# SOC_mcu.net
KiCad netlist of a schematic drawn in EAGLE
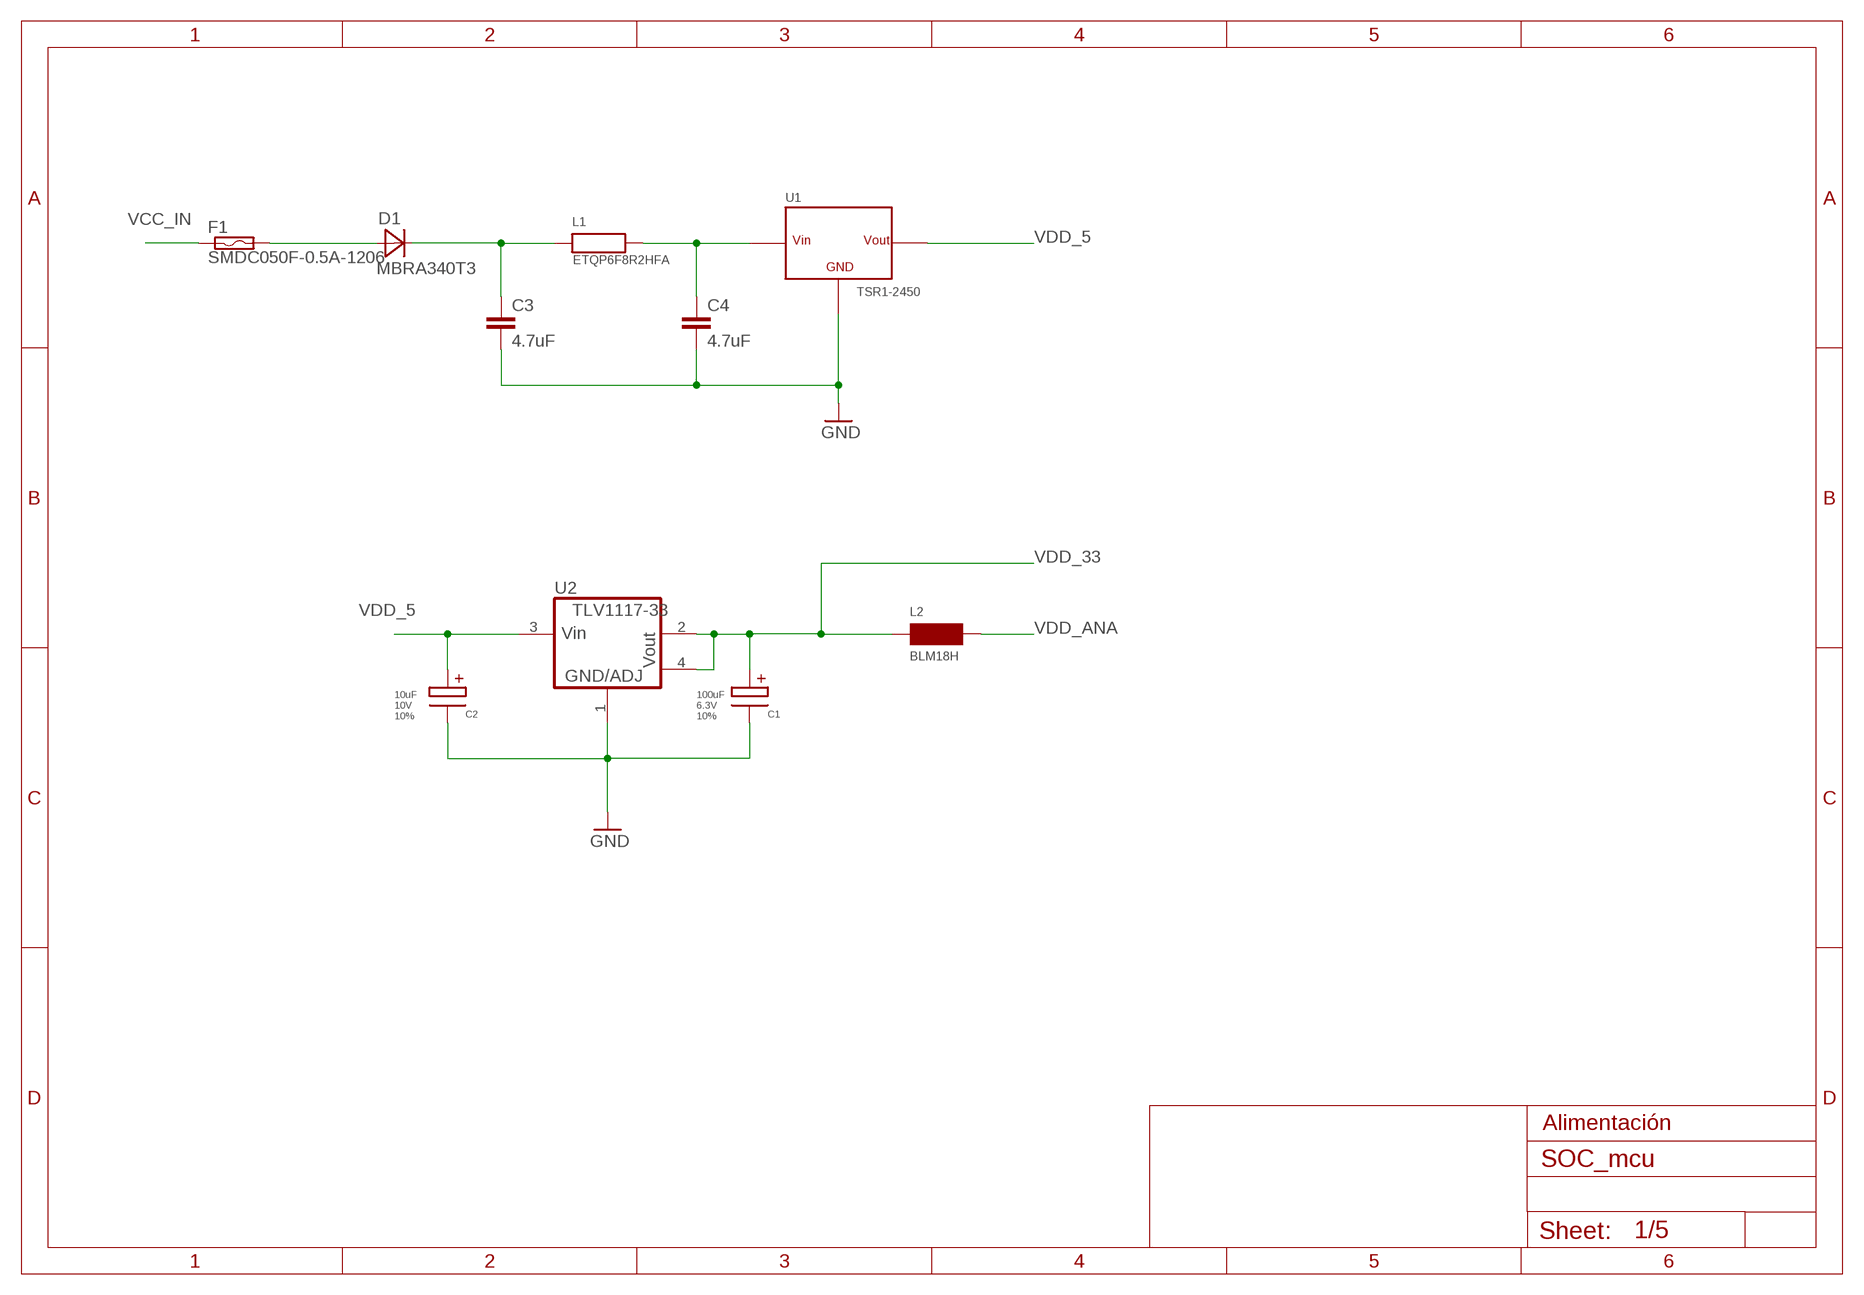
[diagram p0: schematic, sheet 1]
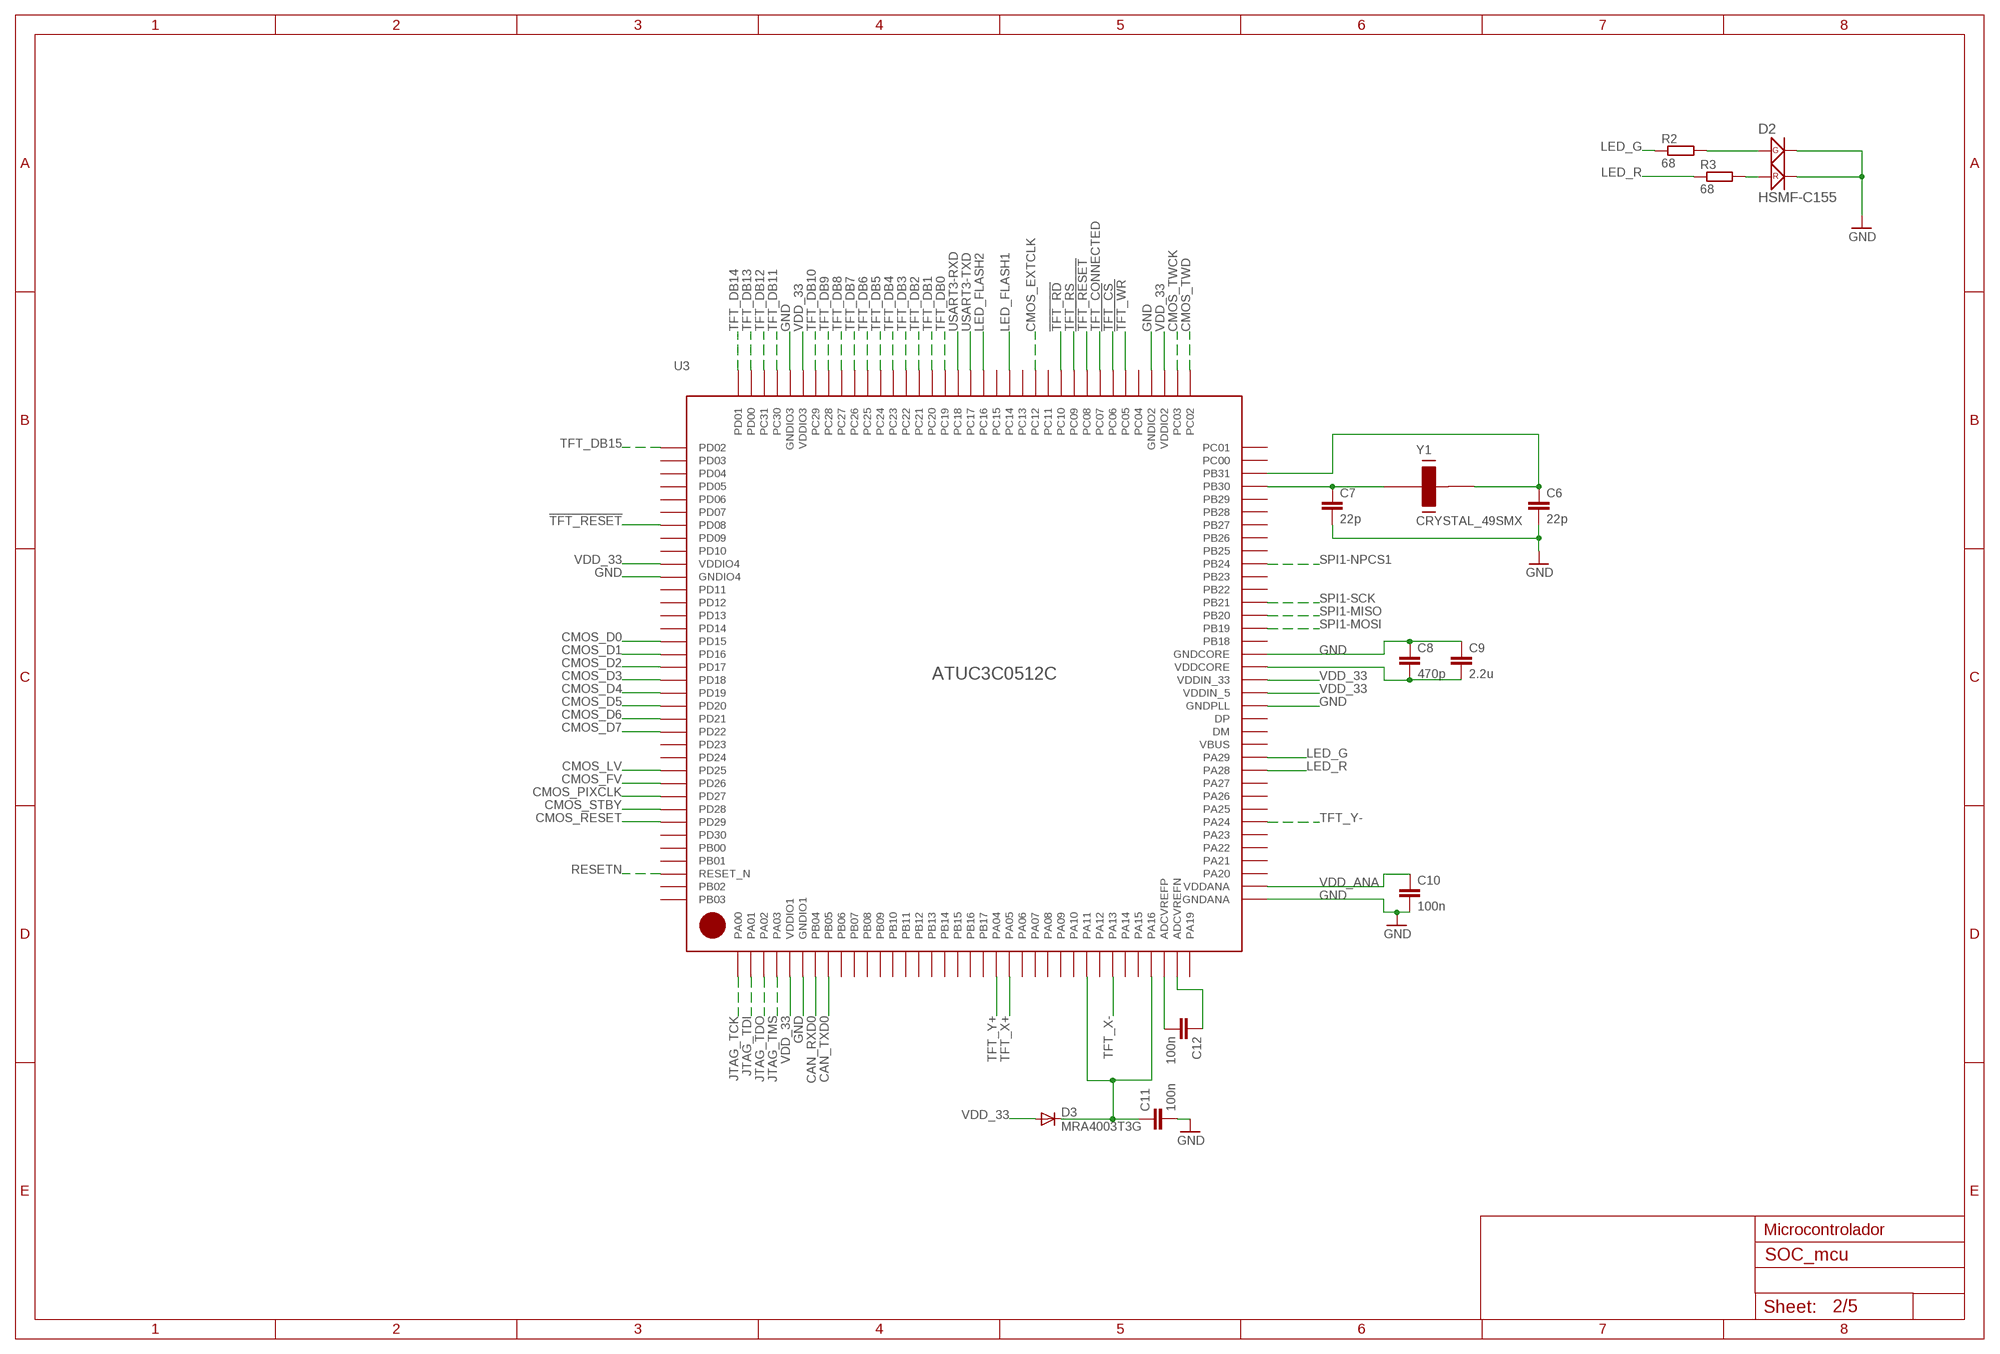
[diagram p1: schematic, sheet 2]
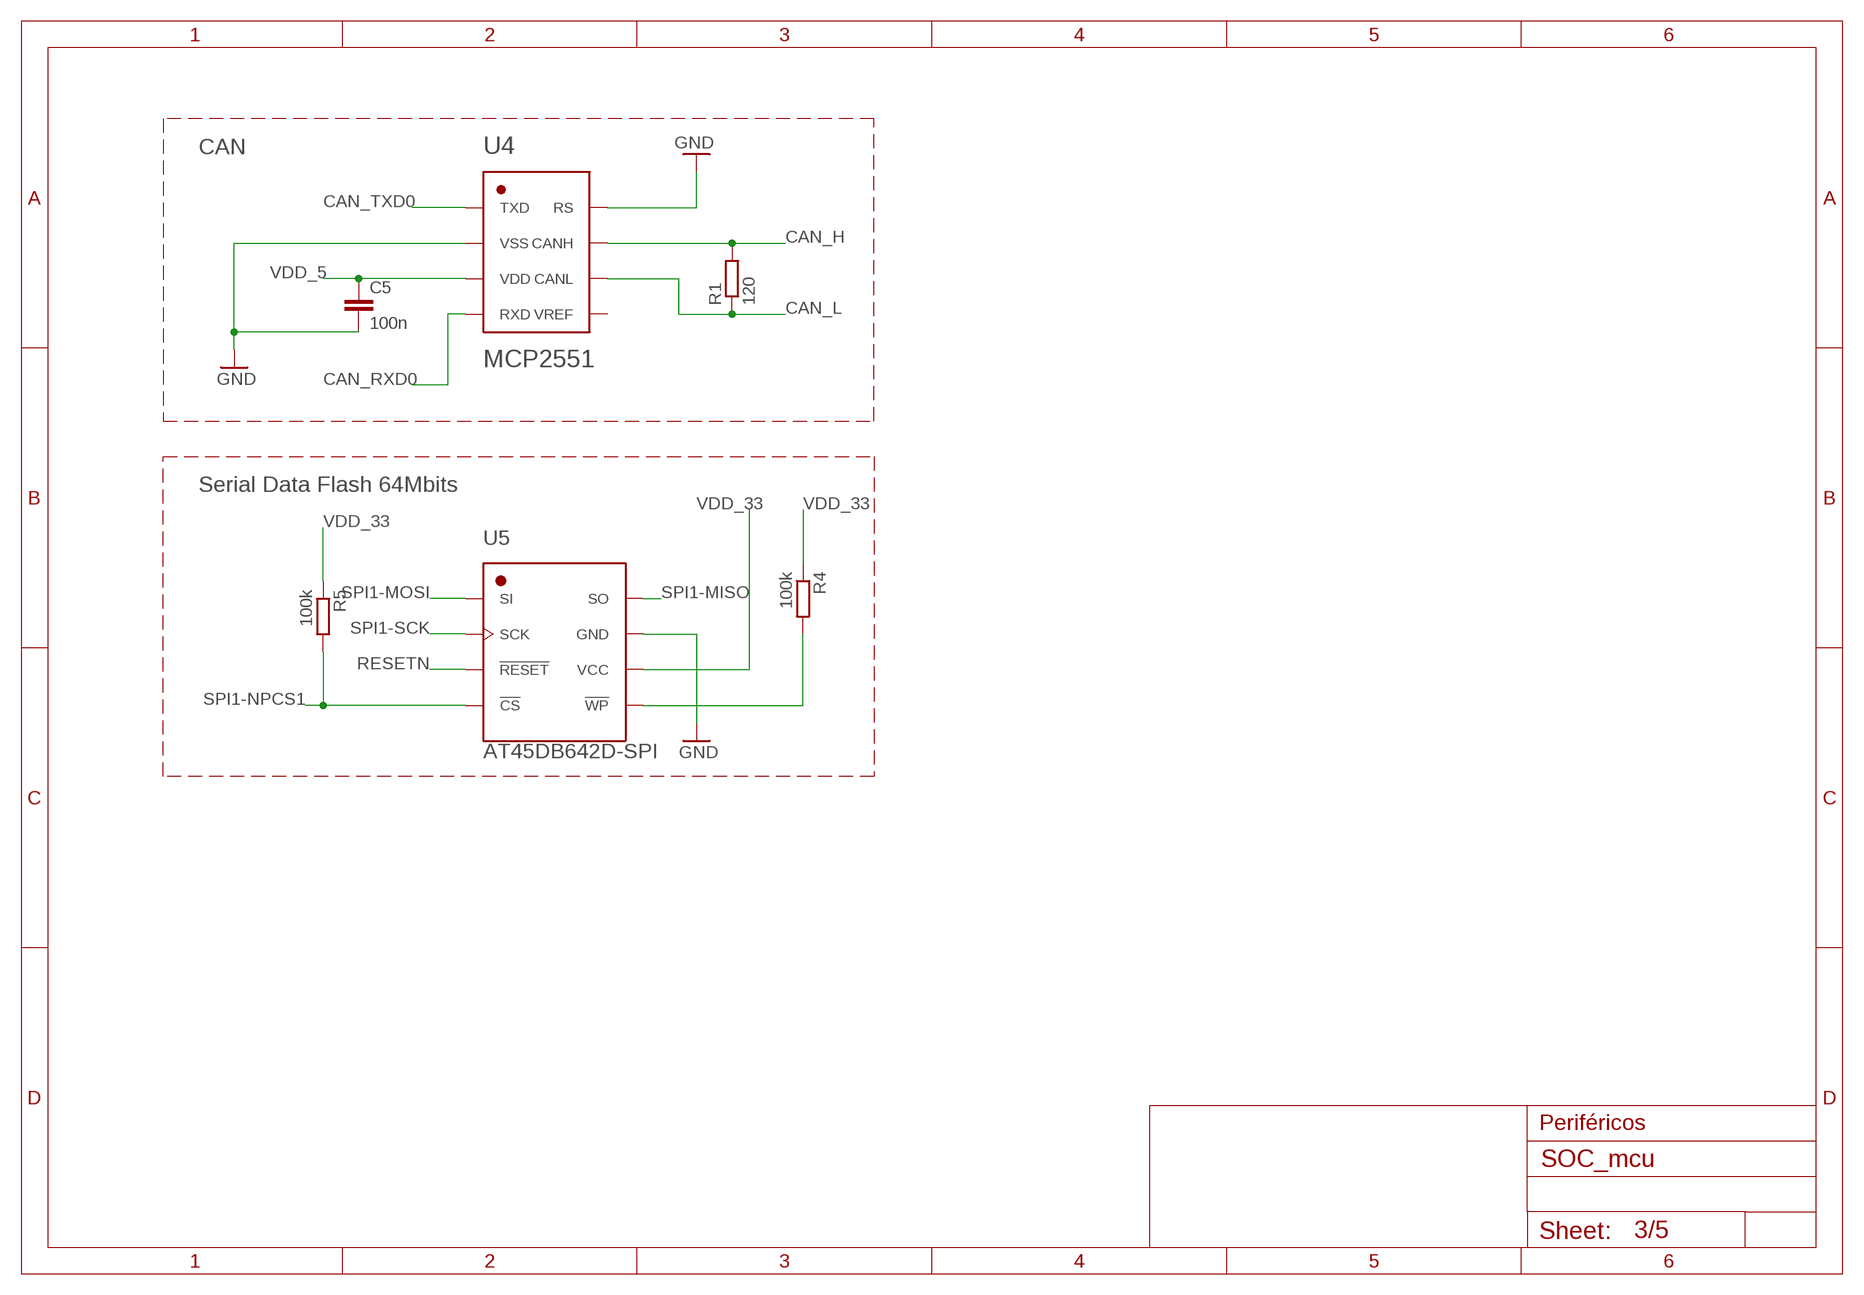
[diagram p2: schematic, sheet 3]
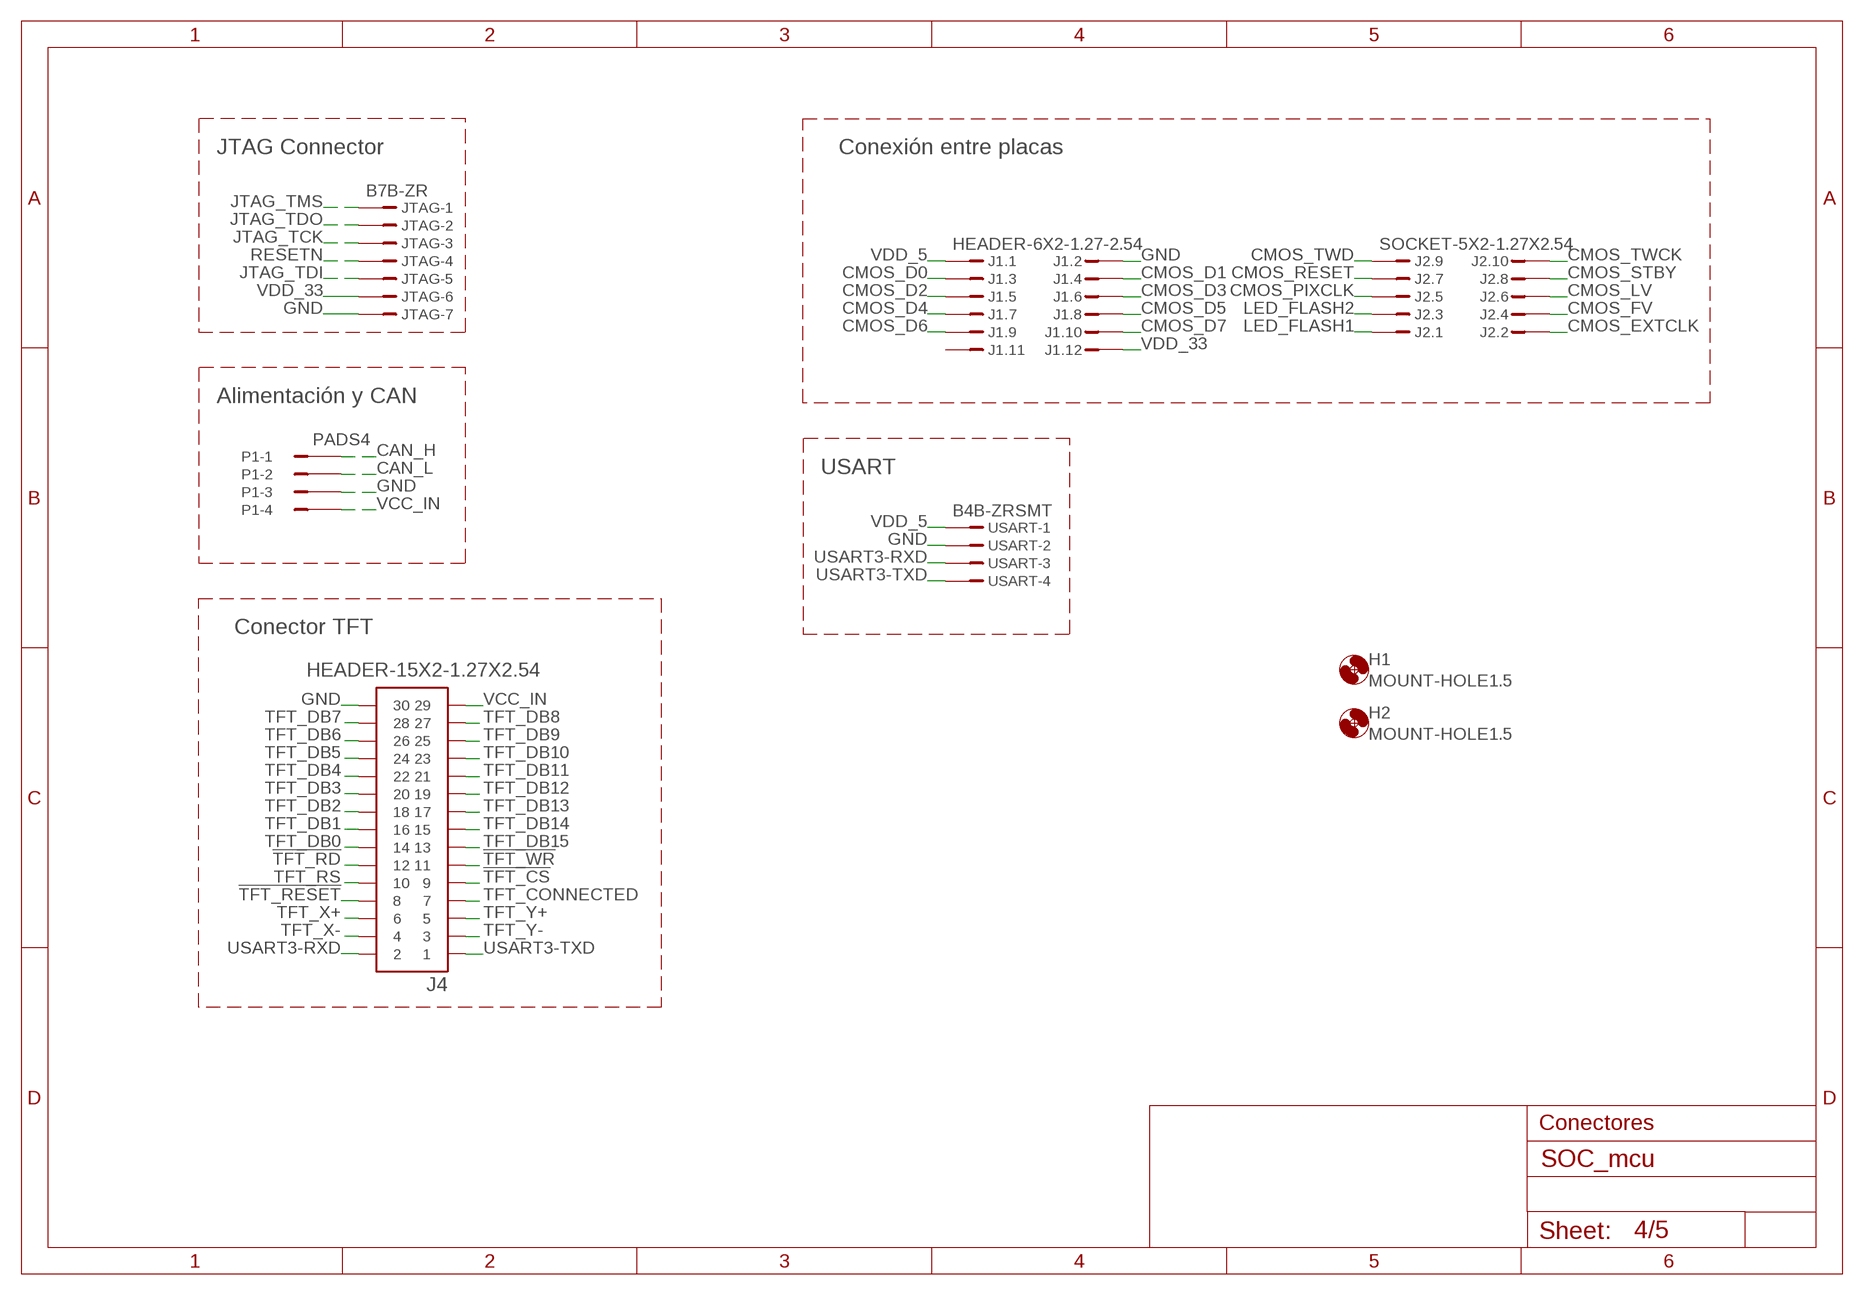
[diagram p3: schematic, sheet 4]
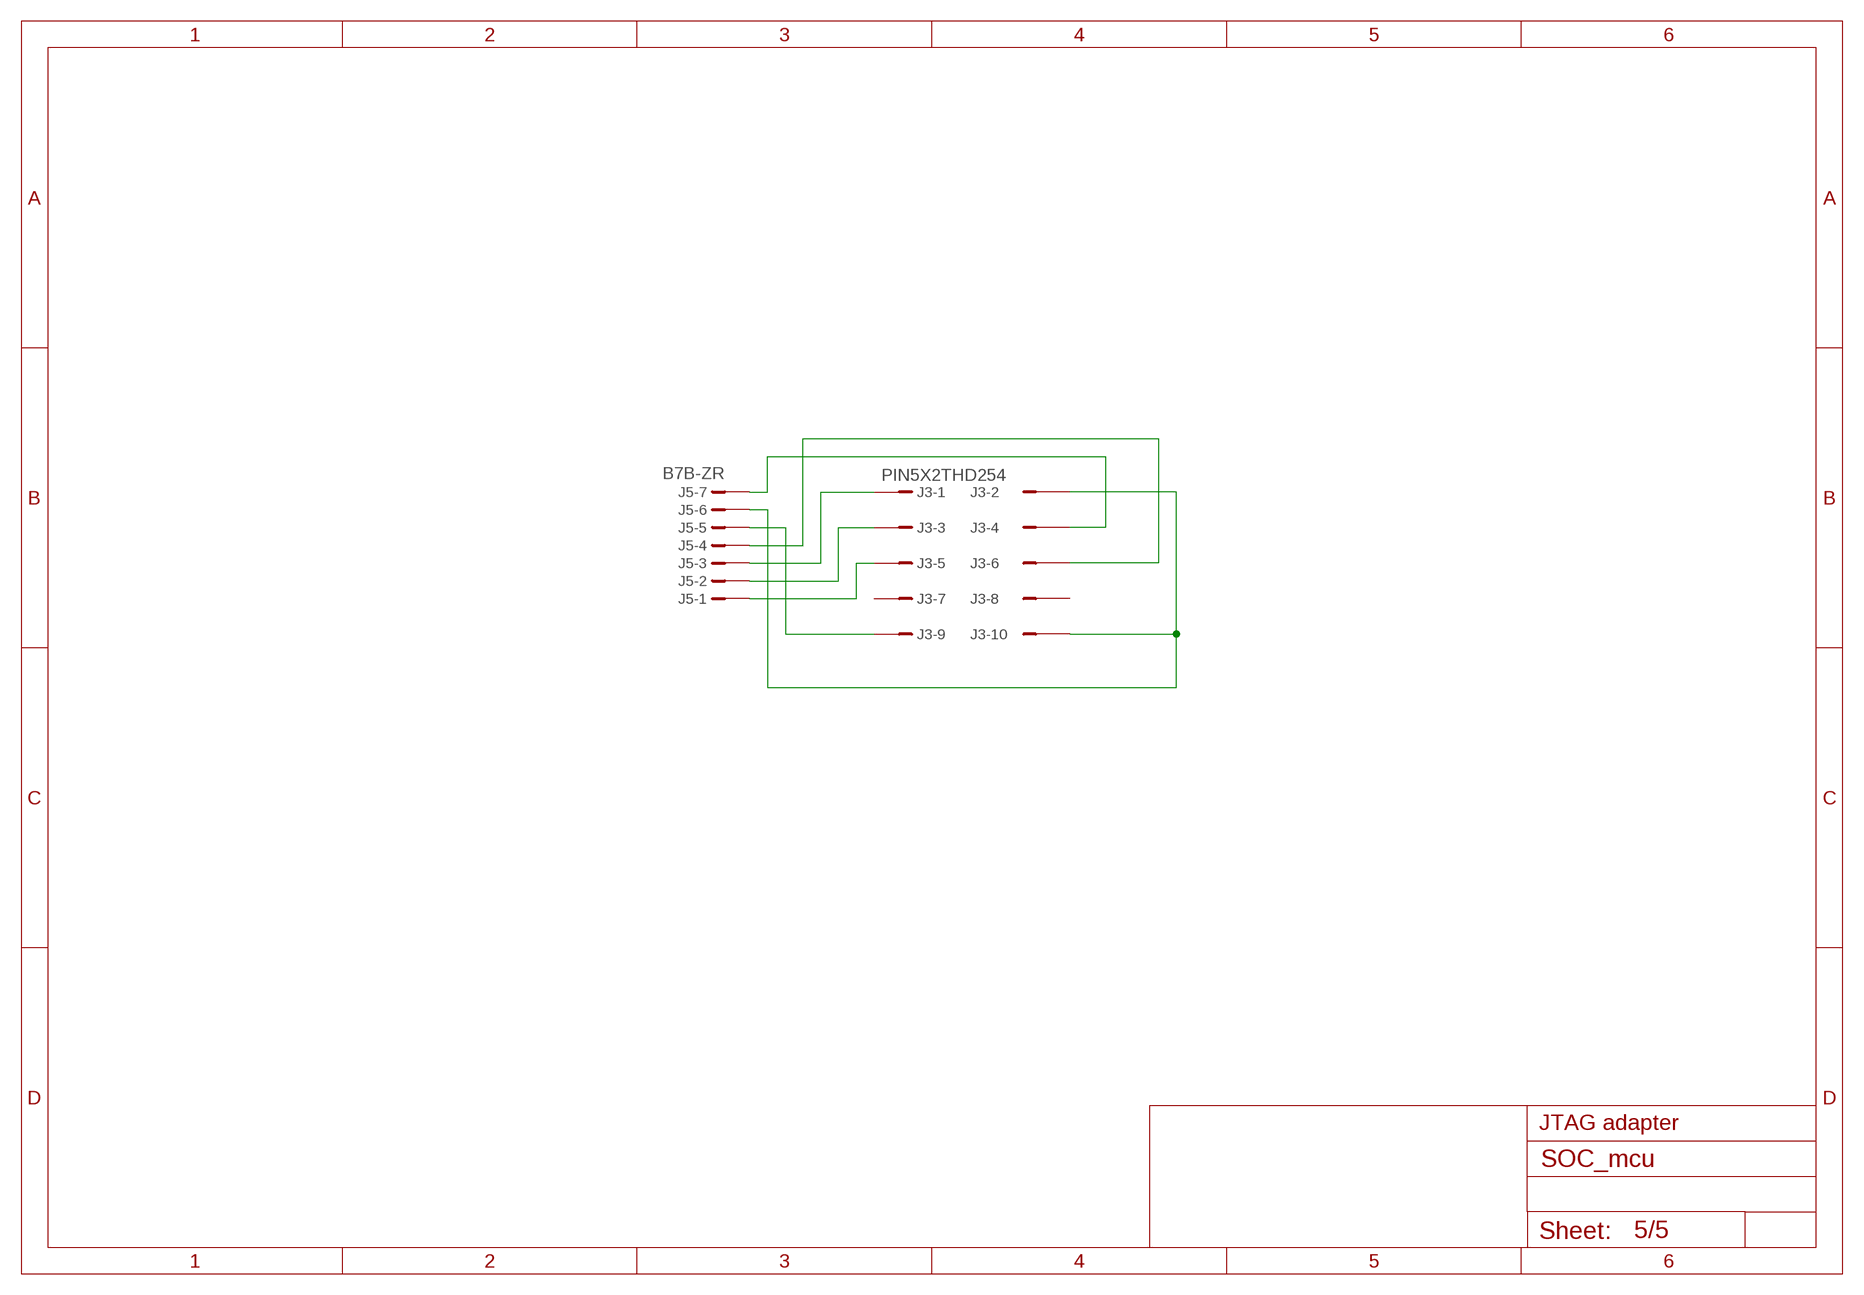
[diagram p4: schematic, sheet 5]

(export (version "E")
  (design (tool "Eeschema 10.0.6"))
  (components
    (comp (ref "C5")
      (value "100n")
      (footprint "eagle-import:C0603")
      (libsource (lib "eagle-import") (part "C-EUC0603"))
    )
    (comp (ref "R1")
      (value "120")
      (footprint "eagle-import:R0805")
      (libsource (lib "eagle-import") (part "R-EU_R0805"))
    )
    (comp (ref "R4")
      (value "100k")
      (footprint "eagle-import:R0603")
      (libsource (lib "eagle-import") (part "R-EU_R0603"))
    )
    (comp (ref "R5")
      (value "100k")
      (footprint "eagle-import:R0603")
      (libsource (lib "eagle-import") (part "R-EU_R0603"))
    )
    (comp (ref "U4")
      (value "MCP2551")
      (footprint "eagle-import:SO08")
      (libsource (lib "eagle-import") (part "MCP2551"))
    )
    (comp (ref "U5")
      (value "AT45DB642D-SPI")
      (footprint "eagle-import:8CN3")
      (libsource (lib "eagle-import") (part "AT45DB642D-SPI"))
    )
    (comp (ref "C1")
      (value "100uF")
      (footprint "eagle-import:3528-21")
      (fields
        (field (name "MPN") "293D107X96R3B2TE3")
        (field (name "TOLERANCE") "10%")
        (field (name "VOLTAGE") "6.3V")
      )
      (libsource (lib "eagle-import") (part "C293DB100U-6V3-10%-"))
    )
    (comp (ref "C2")
      (value "10uF")
      (footprint "eagle-import:3528-21")
      (fields
        (field (name "MPN") "293D106X9010B2TE3")
        (field (name "TOLERANCE") "10%")
        (field (name "VOLTAGE") "10V")
      )
      (libsource (lib "eagle-import") (part "C293DB10U-10V-10%-"))
    )
    (comp (ref "C3")
      (value "4.7uF")
      (footprint "eagle-import:C0805")
      (libsource (lib "eagle-import") (part "C-EUC0805"))
    )
    (comp (ref "C4")
      (value "4.7uF")
      (footprint "eagle-import:C0805")
      (libsource (lib "eagle-import") (part "C-EUC0805"))
    )
    (comp (ref "D1")
      (value "MBRA340T3")
      (footprint "eagle-import:SMA")
      (libsource (lib "eagle-import") (part "MBRA340T3"))
    )
    (comp (ref "F1")
      (value "SMDC050F-0.5A-1206")
      (footprint "eagle-import:1206")
      (fields (field (name "MPN") "NANOSMDC050F/13.2"))
      (libsource (lib "eagle-import") (part "SMDC050F-12060.5A-"))
    )
    (comp (ref "L1")
      (value "ETQP6F8R2HFA")
      (footprint "eagle-import:PAN_COIL_CHOKE")
      (libsource (lib "eagle-import") (part "ETQP6F8R2HFA"))
    )
    (comp (ref "L2")
      (value "BLM18H")
      (footprint "eagle-import:0603")
      (libsource (lib "eagle-import") (part "BLM18H"))
    )
    (comp (ref "U1")
      (value "TSR1-2450")
      (footprint "eagle-import:TO220V")
      (libsource (lib "eagle-import") (part "TSR1-2450"))
    )
    (comp (ref "U2")
      (value "TLV1117-33")
      (footprint "eagle-import:SOT223")
      (fields
        (field (name "MPN") "TLV1117-CDCY")
        (field (name "MPN_1") "TLV1117-CDCY")
        (field (name "OC_FARNELL") "1494942")
        (field (name "OC_RS") "660-7975 ")
      )
      (libsource (lib "eagle-import") (part "REG111733"))
    )
    (comp (ref "C6")
      (value "22p")
      (footprint "eagle-import:C0603")
      (libsource (lib "eagle-import") (part "C-EUC0603"))
    )
    (comp (ref "C7")
      (value "22p")
      (footprint "eagle-import:C0603")
      (libsource (lib "eagle-import") (part "C-EUC0603"))
    )
    (comp (ref "C8")
      (value "470p")
      (footprint "eagle-import:C0603")
      (libsource (lib "eagle-import") (part "C-EUC0603"))
    )
    (comp (ref "C9")
      (value "2.2u")
      (footprint "eagle-import:C0603")
      (libsource (lib "eagle-import") (part "C-EUC0603"))
    )
    (comp (ref "C10")
      (value "100n")
      (footprint "eagle-import:C0603")
      (libsource (lib "eagle-import") (part "C-EUC0603"))
    )
    (comp (ref "C11")
      (value "100n")
      (footprint "eagle-import:C0603")
      (libsource (lib "eagle-import") (part "C-EUC0603"))
    )
    (comp (ref "C12")
      (value "100n")
      (footprint "eagle-import:C0603")
      (libsource (lib "eagle-import") (part "C-EUC0603"))
    )
    (comp (ref "D2")
      (value "HSMF-C155")
      (footprint "eagle-import:HSMF-C")
      (libsource (lib "eagle-import") (part "HSMF-C155"))
    )
    (comp (ref "D3")
      (value "MRA4003T3G")
      (footprint "eagle-import:DO214AC")
      (libsource (lib "eagle-import") (part "DIODE-DO214AC"))
    )
    (comp (ref "R2")
      (value "68")
      (footprint "eagle-import:R0603")
      (libsource (lib "eagle-import") (part "R-EU_R0603"))
    )
    (comp (ref "R3")
      (value "68")
      (footprint "eagle-import:R0603")
      (libsource (lib "eagle-import") (part "R-EU_R0603"))
    )
    (comp (ref "U3")
      (value "ATUC3C0512C")
      (footprint "eagle-import:TQFP144")
      (libsource (lib "eagle-import") (part "ATUC3C0512C"))
    )
    (comp (ref "Y1")
      (value "CRYSTAL_49SMX")
      (footprint "eagle-import:HC49UP")
      (libsource (lib "eagle-import") (part "CRYSTAL_49SMX"))
    )
    (comp (ref "J3")
      (value "PIN5X2THD254")
      (footprint "eagle-import:5X2THD254")
      (libsource (lib "eagle-import") (part "PIN5X2THD254"))
    )
    (comp (ref "J5")
      (value "B7B-ZR")
      (footprint "eagle-import:B7B-ZR")
      (libsource (lib "eagle-import") (part "B7B-ZR"))
    )
    (comp (ref "H1")
      (value "MOUNT-HOLE1.5")
      (footprint "eagle-import:1,5")
      (libsource (lib "eagle-import") (part "MOUNT-HOLE1.5"))
    )
    (comp (ref "H2")
      (value "MOUNT-HOLE1.5")
      (footprint "eagle-import:1,5")
      (libsource (lib "eagle-import") (part "MOUNT-HOLE1.5"))
    )
    (comp (ref "J1")
      (value "HEADER-6X2-1.27-2.54")
      (footprint "eagle-import:HEADER-THD-6X2(1.27X2.54)")
      (libsource (lib "eagle-import") (part "HEADER-6X2-1.27-2.54"))
    )
    (comp (ref "J2")
      (value "SOCKET-5X2-1.27X2.54")
      (footprint "eagle-import:SOCKET-THD-5X2(1.27X2.54)")
      (libsource (lib "eagle-import") (part "SOCKET-5X2-1.27X2.54"))
    )
    (comp (ref "J4")
      (value "HEADER-15X2-1.27X2.54")
      (footprint "eagle-import:HEADER-THD-15X2(1.27X2.54)")
      (libsource (lib "eagle-import") (part "HEADER-15X2-1.27X2.54"))
    )
    (comp (ref "JTAG")
      (value "B7B-ZR")
      (footprint "eagle-import:B7B-ZR")
      (libsource (lib "eagle-import") (part "B7B-ZR"))
    )
    (comp (ref "P1")
      (value "PADS4")
      (footprint "eagle-import:CAN+POWER")
      (libsource (lib "eagle-import") (part "PAD-4"))
    )
    (comp (ref "USART")
      (value "B4B-ZRSMT")
      (footprint "eagle-import:SM4-TF")
      (libsource (lib "eagle-import") (part "B4B-ZRSMT"))
    )
  )
  (nets
    (net (code "1") (name "CAN_H") (class "Default")
      (node (ref "P1") (pin "1") (pinfunction "1_1") (pintype "passive"))
      (node (ref "R1") (pin "2") (pinfunction "2_2") (pintype "passive"))
      (node (ref "U4") (pin "7") (pinfunction "CANH_7") (pintype "bidirectional"))
    )
    (net (code "2") (name "CAN_L") (class "Default")
      (node (ref "P1") (pin "2") (pinfunction "1_2") (pintype "passive"))
      (node (ref "R1") (pin "1") (pinfunction "1_1") (pintype "passive"))
      (node (ref "U4") (pin "6") (pinfunction "CANL_6") (pintype "bidirectional"))
    )
    (net (code "3") (name "CAN_RXD0") (class "Default")
      (node (ref "U3") (pin "7") (pinfunction "PB04_7") (pintype "bidirectional"))
      (node (ref "U4") (pin "4") (pinfunction "RXD_4") (pintype "bidirectional"))
    )
    (net (code "4") (name "CAN_TXD0") (class "Default")
      (node (ref "U3") (pin "8") (pinfunction "PB05_8") (pintype "bidirectional"))
      (node (ref "U4") (pin "1") (pinfunction "TXD_1") (pintype "bidirectional"))
    )
    (net (code "5") (name "CMOS_D0") (class "Default")
      (node (ref "J1") (pin "3") (pinfunction "1_3") (pintype "passive"))
      (node (ref "U3") (pin "124") (pinfunction "PD15_124") (pintype "bidirectional"))
    )
    (net (code "6") (name "CMOS_D1") (class "Default")
      (node (ref "J1") (pin "4") (pinfunction "1_4") (pintype "passive"))
      (node (ref "U3") (pin "125") (pinfunction "PD16_125") (pintype "bidirectional"))
    )
    (net (code "7") (name "CMOS_D2") (class "Default")
      (node (ref "J1") (pin "5") (pinfunction "1_5") (pintype "passive"))
      (node (ref "U3") (pin "126") (pinfunction "PD17_126") (pintype "bidirectional"))
    )
    (net (code "8") (name "CMOS_D3") (class "Default")
      (node (ref "J1") (pin "6") (pinfunction "1_6") (pintype "passive"))
      (node (ref "U3") (pin "127") (pinfunction "PD18_127") (pintype "bidirectional"))
    )
    (net (code "9") (name "CMOS_D4") (class "Default")
      (node (ref "J1") (pin "7") (pinfunction "1_7") (pintype "passive"))
      (node (ref "U3") (pin "128") (pinfunction "PD19_128") (pintype "bidirectional"))
    )
    (net (code "10") (name "CMOS_D5") (class "Default")
      (node (ref "J1") (pin "8") (pinfunction "1_8") (pintype "passive"))
      (node (ref "U3") (pin "129") (pinfunction "PD20_129") (pintype "bidirectional"))
    )
    (net (code "11") (name "CMOS_D6") (class "Default")
      (node (ref "J1") (pin "9") (pinfunction "1_9") (pintype "passive"))
      (node (ref "U3") (pin "130") (pinfunction "PD21_130") (pintype "bidirectional"))
    )
    (net (code "12") (name "CMOS_D7") (class "Default")
      (node (ref "J1") (pin "10") (pinfunction "1_10") (pintype "passive"))
      (node (ref "U3") (pin "131") (pinfunction "PD22_131") (pintype "bidirectional"))
    )
    (net (code "13") (name "CMOS_EXTCLK") (class "Default")
      (node (ref "J2") (pin "P2") (pinfunction "1_P2") (pintype "passive"))
      (node (ref "U3") (pin "85") (pinfunction "PC12_85") (pintype "bidirectional"))
    )
    (net (code "14") (name "CMOS_FV") (class "Default")
      (node (ref "J2") (pin "P4") (pinfunction "1_P4") (pintype "passive"))
      (node (ref "U3") (pin "135") (pinfunction "PD26_135") (pintype "bidirectional"))
    )
    (net (code "15") (name "CMOS_LV") (class "Default")
      (node (ref "J2") (pin "P6") (pinfunction "1_P6") (pintype "passive"))
      (node (ref "U3") (pin "134") (pinfunction "PD25_134") (pintype "bidirectional"))
    )
    (net (code "16") (name "CMOS_PIXCLK") (class "Default")
      (node (ref "J2") (pin "P5") (pinfunction "1_P5") (pintype "passive"))
      (node (ref "U3") (pin "136") (pinfunction "PD27_136") (pintype "bidirectional"))
    )
    (net (code "17") (name "CMOS_RESET") (class "Default")
      (node (ref "J2") (pin "P7") (pinfunction "1_P7") (pintype "passive"))
      (node (ref "U3") (pin "138") (pinfunction "PD29_138") (pintype "bidirectional"))
    )
    (net (code "18") (name "CMOS_STBY") (class "Default")
      (node (ref "J2") (pin "P8") (pinfunction "1_P8") (pintype "passive"))
      (node (ref "U3") (pin "137") (pinfunction "PD28_137") (pintype "bidirectional"))
    )
    (net (code "19") (name "CMOS_TWCK") (class "Default")
      (node (ref "J2") (pin "P10") (pinfunction "1_P10") (pintype "passive"))
      (node (ref "U3") (pin "74") (pinfunction "PC03_74") (pintype "bidirectional"))
    )
    (net (code "20") (name "CMOS_TWD") (class "Default")
      (node (ref "J2") (pin "P9") (pinfunction "1_P9") (pintype "passive"))
      (node (ref "U3") (pin "73") (pinfunction "PC02_73") (pintype "bidirectional"))
    )
    (net (code "21") (name "GND") (class "Default")
      (node (ref "C1") (pin "NEG") (pinfunction "NEG_NEG") (pintype "bidirectional"))
      (node (ref "C10") (pin "2") (pinfunction "2_2") (pintype "passive"))
      (node (ref "C11") (pin "2") (pinfunction "2_2") (pintype "passive"))
      (node (ref "C2") (pin "NEG") (pinfunction "NEG_NEG") (pintype "bidirectional"))
      (node (ref "C3") (pin "2") (pinfunction "2_2") (pintype "passive"))
      (node (ref "C4") (pin "2") (pinfunction "2_2") (pintype "passive"))
      (node (ref "C5") (pin "2") (pinfunction "2_2") (pintype "passive"))
      (node (ref "C6") (pin "2") (pinfunction "2_2") (pintype "passive"))
      (node (ref "C7") (pin "2") (pinfunction "2_2") (pintype "passive"))
      (node (ref "C8") (pin "1") (pinfunction "1_1") (pintype "passive"))
      (node (ref "C9") (pin "1") (pinfunction "1_1") (pintype "passive"))
      (node (ref "D2") (pin "2") (pinfunction "2_2") (pintype "bidirectional"))
      (node (ref "D2") (pin "4") (pinfunction "4_4") (pintype "bidirectional"))
      (node (ref "J1") (pin "2") (pinfunction "1_2") (pintype "passive"))
      (node (ref "J4") (pin "30") (pinfunction "30_30") (pintype "bidirectional"))
      (node (ref "JTAG") (pin "7") (pinfunction "1_7") (pintype "passive"))
      (node (ref "P1") (pin "3") (pinfunction "1_3") (pintype "passive"))
      (node (ref "U1") (pin "2") (pinfunction "GND_2") (pintype "bidirectional"))
      (node (ref "U2") (pin "1") (pinfunction "GND_1") (pintype "bidirectional"))
      (node (ref "U3") (pin "104") (pinfunction "GNDIO3_104") (pintype "bidirectional"))
      (node (ref "U3") (pin "119") (pinfunction "GNDIO4_119") (pintype "bidirectional"))
      (node (ref "U3") (pin "37") (pinfunction "GNDANA_37") (pintype "bidirectional"))
      (node (ref "U3") (pin "52") (pinfunction "GNDPLL_52") (pintype "bidirectional"))
      (node (ref "U3") (pin "56") (pinfunction "GNDCORE_56") (pintype "bidirectional"))
      (node (ref "U3") (pin "6") (pinfunction "GNDIO1_6") (pintype "bidirectional"))
      (node (ref "U3") (pin "76") (pinfunction "GNDIO2_76") (pintype "bidirectional"))
      (node (ref "U4") (pin "2") (pinfunction "VSS_2") (pintype "bidirectional"))
      (node (ref "U4") (pin "8") (pinfunction "RS_8") (pintype "bidirectional"))
      (node (ref "U5") (pin "7") (pinfunction "GND_7") (pintype "bidirectional"))
      (node (ref "USART") (pin "2") (pinfunction "1_2") (pintype "passive"))
    )
    (net (code "22") (name "JTAG_TCK") (class "Default")
      (node (ref "JTAG") (pin "3") (pinfunction "1_3") (pintype "passive"))
      (node (ref "U3") (pin "1") (pinfunction "PA00_1") (pintype "bidirectional"))
    )
    (net (code "23") (name "JTAG_TDI") (class "Default")
      (node (ref "JTAG") (pin "5") (pinfunction "1_5") (pintype "passive"))
      (node (ref "U3") (pin "2") (pinfunction "PA01_2") (pintype "bidirectional"))
    )
    (net (code "24") (name "JTAG_TDO") (class "Default")
      (node (ref "JTAG") (pin "2") (pinfunction "1_2") (pintype "passive"))
      (node (ref "U3") (pin "3") (pinfunction "PA02_3") (pintype "bidirectional"))
    )
    (net (code "25") (name "JTAG_TMS") (class "Default")
      (node (ref "JTAG") (pin "1") (pinfunction "1_1") (pintype "passive"))
      (node (ref "U3") (pin "4") (pinfunction "PA03_4") (pintype "bidirectional"))
    )
    (net (code "26") (name "LED_FLASH1") (class "Default")
      (node (ref "J2") (pin "P1") (pinfunction "1_P1") (pintype "passive"))
      (node (ref "U3") (pin "87") (pinfunction "PC14_87") (pintype "bidirectional"))
    )
    (net (code "27") (name "LED_FLASH2") (class "Default")
      (node (ref "J2") (pin "P3") (pinfunction "1_P3") (pintype "passive"))
      (node (ref "U3") (pin "89") (pinfunction "PC16_89") (pintype "bidirectional"))
    )
    (net (code "28") (name "LED_G") (class "Default")
      (node (ref "R2") (pin "1") (pinfunction "1_1") (pintype "passive"))
      (node (ref "U3") (pin "48") (pinfunction "PA29_48") (pintype "bidirectional"))
    )
    (net (code "29") (name "LED_R") (class "Default")
      (node (ref "R3") (pin "1") (pinfunction "1_1") (pintype "passive"))
      (node (ref "U3") (pin "47") (pinfunction "PA28_47") (pintype "bidirectional"))
    )
    (net (code "30") (name "Net-(D1-PadA)") (class "Default")
      (node (ref "D1") (pin "A") (pinfunction "A_A") (pintype "passive"))
      (node (ref "F1") (pin "2") (pinfunction "2_2") (pintype "passive"))
    )
    (net (code "31") (name "Net-(D2-Pad1)") (class "Default")
      (node (ref "D2") (pin "1") (pinfunction "1_1") (pintype "bidirectional"))
      (node (ref "R2") (pin "2") (pinfunction "2_2") (pintype "passive"))
    )
    (net (code "32") (name "Net-(D2-Pad3)") (class "Default")
      (node (ref "D2") (pin "3") (pinfunction "3_3") (pintype "bidirectional"))
      (node (ref "R3") (pin "2") (pinfunction "2_2") (pintype "passive"))
    )
    (net (code "33") (name "Net-(J3B-1)") (class "Default")
      (node (ref "J3") (pin "10") (pinfunction "1_10") (pintype "passive"))
      (node (ref "J3") (pin "2") (pinfunction "1_2") (pintype "passive"))
      (node (ref "J5") (pin "6") (pinfunction "1_6") (pintype "passive"))
    )
    (net (code "34") (name "Net-(J3D-1)") (class "Default")
      (node (ref "J3") (pin "3") (pinfunction "1_3") (pintype "passive"))
      (node (ref "J5") (pin "2") (pinfunction "1_2") (pintype "passive"))
    )
    (net (code "35") (name "Net-(J3E-1)") (class "Default")
      (node (ref "J3") (pin "4") (pinfunction "1_4") (pintype "passive"))
      (node (ref "J5") (pin "7") (pinfunction "1_7") (pintype "passive"))
    )
    (net (code "36") (name "Net-(J3F-1)") (class "Default")
      (node (ref "J3") (pin "5") (pinfunction "1_5") (pintype "passive"))
      (node (ref "J5") (pin "1") (pinfunction "1_1") (pintype "passive"))
    )
    (net (code "37") (name "Net-(J3G-1)") (class "Default")
      (node (ref "J3") (pin "6") (pinfunction "1_6") (pintype "passive"))
      (node (ref "J5") (pin "4") (pinfunction "1_4") (pintype "passive"))
    )
    (net (code "38") (name "Net-(J3J-1)") (class "Default")
      (node (ref "J3") (pin "9") (pinfunction "1_9") (pintype "passive"))
      (node (ref "J5") (pin "5") (pinfunction "1_5") (pintype "passive"))
    )
    (net (code "39") (name "Net-(J5C-1)") (class "Default")
      (node (ref "J3") (pin "1") (pinfunction "1_1") (pintype "passive"))
      (node (ref "J5") (pin "3") (pinfunction "1_3") (pintype "passive"))
    )
    (net (code "40") (name "Net-(L1-P$1)") (class "Default")
      (node (ref "C3") (pin "1") (pinfunction "1_1") (pintype "passive"))
      (node (ref "D1") (pin "C") (pinfunction "C_C") (pintype "passive"))
      (node (ref "L1") (pin "1") (pinfunction "P$1_1") (pintype "bidirectional"))
    )
    (net (code "41") (name "Net-(L1-P$2)") (class "Default")
      (node (ref "C4") (pin "1") (pinfunction "1_1") (pintype "passive"))
      (node (ref "L1") (pin "2") (pinfunction "P$2_2") (pintype "bidirectional"))
      (node (ref "U1") (pin "1") (pinfunction "+VIN_1") (pintype "bidirectional"))
    )
    (net (code "42") (name "Net-(U3-ADCVREFN)") (class "Default")
      (node (ref "C12") (pin "1") (pinfunction "1_1") (pintype "passive"))
      (node (ref "U3") (pin "35") (pinfunction "ADCVREFN_35") (pintype "bidirectional"))
    )
    (net (code "43") (name "Net-(U3-ADCVREFP)") (class "Default")
      (node (ref "C12") (pin "2") (pinfunction "2_2") (pintype "passive"))
      (node (ref "U3") (pin "34") (pinfunction "ADCVREFP_34") (pintype "bidirectional"))
    )
    (net (code "44") (name "Net-(U3-PA11)") (class "Default")
      (node (ref "C11") (pin "1") (pinfunction "1_1") (pintype "passive"))
      (node (ref "D3") (pin "C") (pinfunction "C_C") (pintype "passive"))
      (node (ref "U3") (pin "28") (pinfunction "PA11_28") (pintype "bidirectional"))
      (node (ref "U3") (pin "33") (pinfunction "PA16_33") (pintype "bidirectional"))
    )
    (net (code "45") (name "Net-(U3-PB30)") (class "Default")
      (node (ref "C7") (pin "1") (pinfunction "1_1") (pintype "passive"))
      (node (ref "U3") (pin "69") (pinfunction "PB30_69") (pintype "bidirectional"))
      (node (ref "Y1") (pin "1") (pinfunction "1_1") (pintype "bidirectional"))
    )
    (net (code "46") (name "Net-(U3-PB31)") (class "Default")
      (node (ref "C6") (pin "1") (pinfunction "1_1") (pintype "passive"))
      (node (ref "U3") (pin "70") (pinfunction "PB31_70") (pintype "bidirectional"))
      (node (ref "Y1") (pin "2") (pinfunction "2_2") (pintype "bidirectional"))
    )
    (net (code "47") (name "Net-(U3-VDDCORE)") (class "Default")
      (node (ref "C8") (pin "2") (pinfunction "2_2") (pintype "passive"))
      (node (ref "C9") (pin "2") (pinfunction "2_2") (pintype "passive"))
      (node (ref "U3") (pin "55") (pinfunction "VDDCORE_55") (pintype "bidirectional"))
    )
    (net (code "48") (name "Net-(U5-~{WP})") (class "Default")
      (node (ref "R4") (pin "2") (pinfunction "2_2") (pintype "passive"))
      (node (ref "U5") (pin "5") (pinfunction "~{WP}_5") (pintype "bidirectional"))
    )
    (net (code "49") (name "RESETN") (class "Default")
      (node (ref "JTAG") (pin "4") (pinfunction "1_4") (pintype "passive"))
      (node (ref "U3") (pin "142") (pinfunction "RESET_N_142") (pintype "bidirectional"))
      (node (ref "U5") (pin "3") (pinfunction "~{RESET}_3") (pintype "bidirectional"))
    )
    (net (code "50") (name "SPI1-MISO") (class "Default")
      (node (ref "U3") (pin "59") (pinfunction "PB20_59") (pintype "bidirectional"))
      (node (ref "U5") (pin "8") (pinfunction "SO_8") (pintype "bidirectional"))
    )
    (net (code "51") (name "SPI1-MOSI") (class "Default")
      (node (ref "U3") (pin "58") (pinfunction "PB19_58") (pintype "bidirectional"))
      (node (ref "U5") (pin "1") (pinfunction "SI_1") (pintype "bidirectional"))
    )
    (net (code "52") (name "SPI1-NPCS1") (class "Default")
      (node (ref "R5") (pin "2") (pinfunction "2_2") (pintype "passive"))
      (node (ref "U3") (pin "63") (pinfunction "PB24_63") (pintype "bidirectional"))
      (node (ref "U5") (pin "4") (pinfunction "~{CS}_4") (pintype "bidirectional"))
    )
    (net (code "53") (name "SPI1-SCK") (class "Default")
      (node (ref "U3") (pin "60") (pinfunction "PB21_60") (pintype "bidirectional"))
      (node (ref "U5") (pin "2") (pinfunction "SCK_2") (pintype "bidirectional"))
    )
    (net (code "54") (name "TFT_CONNECTED") (class "Default")
      (node (ref "J4") (pin "7") (pinfunction "7_7") (pintype "bidirectional"))
      (node (ref "U3") (pin "80") (pinfunction "PC07_80") (pintype "bidirectional"))
    )
    (net (code "55") (name "TFT_DB0") (class "Default")
      (node (ref "J4") (pin "14") (pinfunction "14_14") (pintype "bidirectional"))
      (node (ref "U3") (pin "92") (pinfunction "PC19_92") (pintype "bidirectional"))
    )
    (net (code "56") (name "TFT_DB1") (class "Default")
      (node (ref "J4") (pin "16") (pinfunction "16_16") (pintype "bidirectional"))
      (node (ref "U3") (pin "93") (pinfunction "PC20_93") (pintype "bidirectional"))
    )
    (net (code "57") (name "TFT_DB2") (class "Default")
      (node (ref "J4") (pin "18") (pinfunction "18_18") (pintype "bidirectional"))
      (node (ref "U3") (pin "94") (pinfunction "PC21_94") (pintype "bidirectional"))
    )
    (net (code "58") (name "TFT_DB3") (class "Default")
      (node (ref "J4") (pin "20") (pinfunction "20_20") (pintype "bidirectional"))
      (node (ref "U3") (pin "95") (pinfunction "PC22_95") (pintype "bidirectional"))
    )
    (net (code "59") (name "TFT_DB4") (class "Default")
      (node (ref "J4") (pin "22") (pinfunction "22_22") (pintype "bidirectional"))
      (node (ref "U3") (pin "96") (pinfunction "PC23_96") (pintype "bidirectional"))
    )
    (net (code "60") (name "TFT_DB5") (class "Default")
      (node (ref "J4") (pin "24") (pinfunction "24_24") (pintype "bidirectional"))
      (node (ref "U3") (pin "97") (pinfunction "PC24_97") (pintype "bidirectional"))
    )
    (net (code "61") (name "TFT_DB6") (class "Default")
      (node (ref "J4") (pin "26") (pinfunction "26_26") (pintype "bidirectional"))
      (node (ref "U3") (pin "98") (pinfunction "PC25_98") (pintype "bidirectional"))
    )
    (net (code "62") (name "TFT_DB7") (class "Default")
      (node (ref "J4") (pin "28") (pinfunction "28_28") (pintype "bidirectional"))
      (node (ref "U3") (pin "99") (pinfunction "PC26_99") (pintype "bidirectional"))
    )
    (net (code "63") (name "TFT_DB8") (class "Default")
      (node (ref "J4") (pin "27") (pinfunction "27_27") (pintype "bidirectional"))
      (node (ref "U3") (pin "100") (pinfunction "PC27_100") (pintype "bidirectional"))
    )
    (net (code "64") (name "TFT_DB9") (class "Default")
      (node (ref "J4") (pin "25") (pinfunction "25_25") (pintype "bidirectional"))
      (node (ref "U3") (pin "101") (pinfunction "PC28_101") (pintype "bidirectional"))
    )
    (net (code "65") (name "TFT_DB10") (class "Default")
      (node (ref "J4") (pin "23") (pinfunction "23_23") (pintype "bidirectional"))
      (node (ref "U3") (pin "102") (pinfunction "PC29_102") (pintype "bidirectional"))
    )
    (net (code "66") (name "TFT_DB11") (class "Default")
      (node (ref "J4") (pin "21") (pinfunction "21_21") (pintype "bidirectional"))
      (node (ref "U3") (pin "105") (pinfunction "PC30_105") (pintype "bidirectional"))
    )
    (net (code "67") (name "TFT_DB12") (class "Default")
      (node (ref "J4") (pin "19") (pinfunction "19_19") (pintype "bidirectional"))
      (node (ref "U3") (pin "106") (pinfunction "PC31_106") (pintype "bidirectional"))
    )
    (net (code "68") (name "TFT_DB13") (class "Default")
      (node (ref "J4") (pin "17") (pinfunction "17_17") (pintype "bidirectional"))
      (node (ref "U3") (pin "107") (pinfunction "PD00_107") (pintype "bidirectional"))
    )
    (net (code "69") (name "TFT_DB14") (class "Default")
      (node (ref "J4") (pin "15") (pinfunction "15_15") (pintype "bidirectional"))
      (node (ref "U3") (pin "108") (pinfunction "PD01_108") (pintype "bidirectional"))
    )
    (net (code "70") (name "TFT_DB15") (class "Default")
      (node (ref "J4") (pin "13") (pinfunction "13_13") (pintype "bidirectional"))
      (node (ref "U3") (pin "109") (pinfunction "PD02_109") (pintype "bidirectional"))
    )
    (net (code "71") (name "TFT_RS") (class "Default")
      (node (ref "J4") (pin "10") (pinfunction "10_10") (pintype "bidirectional"))
      (node (ref "U3") (pin "82") (pinfunction "PC09_82") (pintype "bidirectional"))
    )
    (net (code "72") (name "TFT_X+") (class "Default")
      (node (ref "J4") (pin "6") (pinfunction "6_6") (pintype "bidirectional"))
      (node (ref "U3") (pin "22") (pinfunction "PA05_22") (pintype "bidirectional"))
    )
    (net (code "73") (name "TFT_X-") (class "Default")
      (node (ref "J4") (pin "4") (pinfunction "4_4") (pintype "bidirectional"))
      (node (ref "U3") (pin "30") (pinfunction "PA13_30") (pintype "bidirectional"))
    )
    (net (code "74") (name "TFT_Y+") (class "Default")
      (node (ref "J4") (pin "5") (pinfunction "5_5") (pintype "bidirectional"))
      (node (ref "U3") (pin "21") (pinfunction "PA04_21") (pintype "bidirectional"))
    )
    (net (code "75") (name "TFT_Y-") (class "Default")
      (node (ref "J4") (pin "3") (pinfunction "3_3") (pintype "bidirectional"))
      (node (ref "U3") (pin "43") (pinfunction "PA24_43") (pintype "bidirectional"))
    )
    (net (code "76") (name "USART3-RXD") (class "Default")
      (node (ref "J4") (pin "2") (pinfunction "2_2") (pintype "bidirectional"))
      (node (ref "U3") (pin "91") (pinfunction "PC18_91") (pintype "bidirectional"))
      (node (ref "USART") (pin "3") (pinfunction "1_3") (pintype "passive"))
    )
    (net (code "77") (name "USART3-TXD") (class "Default")
      (node (ref "J4") (pin "1") (pinfunction "1_1") (pintype "bidirectional"))
      (node (ref "U3") (pin "90") (pinfunction "PC17_90") (pintype "bidirectional"))
      (node (ref "USART") (pin "4") (pinfunction "1_4") (pintype "passive"))
    )
    (net (code "78") (name "VCC_IN") (class "Default")
      (node (ref "F1") (pin "1") (pinfunction "1_1") (pintype "passive"))
      (node (ref "J4") (pin "29") (pinfunction "29_29") (pintype "bidirectional"))
      (node (ref "P1") (pin "4") (pinfunction "1_4") (pintype "passive"))
    )
    (net (code "79") (name "VDD_5") (class "Default")
      (node (ref "C2") (pin "POS") (pinfunction "POS_POS") (pintype "bidirectional"))
      (node (ref "C5") (pin "1") (pinfunction "1_1") (pintype "passive"))
      (node (ref "J1") (pin "1") (pinfunction "1_1") (pintype "passive"))
      (node (ref "U1") (pin "3") (pinfunction "VOUT_3") (pintype "bidirectional"))
      (node (ref "U2") (pin "3") (pinfunction "VIN_3") (pintype "input"))
      (node (ref "U4") (pin "3") (pinfunction "VDD_3") (pintype "bidirectional"))
      (node (ref "USART") (pin "1") (pinfunction "1_1") (pintype "passive"))
    )
    (net (code "80") (name "VDD_33") (class "Default")
      (node (ref "C1") (pin "POS") (pinfunction "POS_POS") (pintype "bidirectional"))
      (node (ref "D3") (pin "A") (pinfunction "A_A") (pintype "passive"))
      (node (ref "J1") (pin "12") (pinfunction "1_12") (pintype "passive"))
      (node (ref "JTAG") (pin "6") (pinfunction "1_6") (pintype "passive"))
      (node (ref "L2") (pin "1") (pinfunction "1_1") (pintype "bidirectional"))
      (node (ref "R4") (pin "1") (pinfunction "1_1") (pintype "passive"))
      (node (ref "R5") (pin "1") (pinfunction "1_1") (pintype "passive"))
      (node (ref "U2") (pin "2") (pinfunction "VOUT_2") (pintype "bidirectional"))
      (node (ref "U2") (pin "4") (pinfunction "VO2_4") (pintype "bidirectional"))
      (node (ref "U3") (pin "103") (pinfunction "VDDIO3_103") (pintype "bidirectional"))
      (node (ref "U3") (pin "118") (pinfunction "VDDIO4_118") (pintype "bidirectional"))
      (node (ref "U3") (pin "5") (pinfunction "VDDIO1_5") (pintype "bidirectional"))
      (node (ref "U3") (pin "53") (pinfunction "VDDIN_5_53") (pintype "bidirectional"))
      (node (ref "U3") (pin "54") (pinfunction "VDDIN_33_54") (pintype "bidirectional"))
      (node (ref "U3") (pin "75") (pinfunction "VDDIO2_75") (pintype "bidirectional"))
      (node (ref "U5") (pin "6") (pinfunction "VCC_6") (pintype "bidirectional"))
    )
    (net (code "81") (name "VDD_ANA") (class "Default")
      (node (ref "C10") (pin "1") (pinfunction "1_1") (pintype "passive"))
      (node (ref "L2") (pin "2") (pinfunction "2_2") (pintype "bidirectional"))
      (node (ref "U3") (pin "38") (pinfunction "VDDANA_38") (pintype "bidirectional"))
    )
    (net (code "82") (name "unconnected-(J1C-1-Pad11)") (class "Default")
      (node (ref "J1") (pin "11") (pinfunction "1_11") (pintype "passive"))
    )
    (net (code "83") (name "unconnected-(J3H-1-Pad7)") (class "Default")
      (node (ref "J3") (pin "7") (pinfunction "1_7") (pintype "passive"))
    )
    (net (code "84") (name "unconnected-(J3I-1-Pad8)") (class "Default")
      (node (ref "J3") (pin "8") (pinfunction "1_8") (pintype "passive"))
    )
    (net (code "85") (name "unconnected-(U3-DM-Pad50)") (class "Default")
      (node (ref "U3") (pin "50") (pinfunction "DM_50") (pintype "bidirectional"))
    )
    (net (code "86") (name "unconnected-(U3-DP-Pad51)") (class "Default")
      (node (ref "U3") (pin "51") (pinfunction "DP_51") (pintype "bidirectional"))
    )
    (net (code "87") (name "unconnected-(U3-PA06-Pad23)") (class "Default")
      (node (ref "U3") (pin "23") (pinfunction "PA06_23") (pintype "bidirectional"))
    )
    (net (code "88") (name "unconnected-(U3-PA07-Pad24)") (class "Default")
      (node (ref "U3") (pin "24") (pinfunction "PA07_24") (pintype "bidirectional"))
    )
    (net (code "89") (name "unconnected-(U3-PA08-Pad25)") (class "Default")
      (node (ref "U3") (pin "25") (pinfunction "PA08_25") (pintype "bidirectional"))
    )
    (net (code "90") (name "unconnected-(U3-PA09-Pad26)") (class "Default")
      (node (ref "U3") (pin "26") (pinfunction "PA09_26") (pintype "bidirectional"))
    )
    (net (code "91") (name "unconnected-(U3-PA10-Pad27)") (class "Default")
      (node (ref "U3") (pin "27") (pinfunction "PA10_27") (pintype "bidirectional"))
    )
    (net (code "92") (name "unconnected-(U3-PA12-Pad29)") (class "Default")
      (node (ref "U3") (pin "29") (pinfunction "PA12_29") (pintype "bidirectional"))
    )
    (net (code "93") (name "unconnected-(U3-PA14-Pad31)") (class "Default")
      (node (ref "U3") (pin "31") (pinfunction "PA14_31") (pintype "bidirectional"))
    )
    (net (code "94") (name "unconnected-(U3-PA15-Pad32)") (class "Default")
      (node (ref "U3") (pin "32") (pinfunction "PA15_32") (pintype "bidirectional"))
    )
    (net (code "95") (name "unconnected-(U3-PA19-Pad36)") (class "Default")
      (node (ref "U3") (pin "36") (pinfunction "PA19_36") (pintype "bidirectional"))
    )
    (net (code "96") (name "unconnected-(U3-PA20-Pad39)") (class "Default")
      (node (ref "U3") (pin "39") (pinfunction "PA20_39") (pintype "bidirectional"))
    )
    (net (code "97") (name "unconnected-(U3-PA21-Pad40)") (class "Default")
      (node (ref "U3") (pin "40") (pinfunction "PA21_40") (pintype "bidirectional"))
    )
    (net (code "98") (name "unconnected-(U3-PA22-Pad41)") (class "Default")
      (node (ref "U3") (pin "41") (pinfunction "PA22_41") (pintype "bidirectional"))
    )
    (net (code "99") (name "unconnected-(U3-PA23-Pad42)") (class "Default")
      (node (ref "U3") (pin "42") (pinfunction "PA23_42") (pintype "bidirectional"))
    )
    (net (code "100") (name "unconnected-(U3-PA25-Pad44)") (class "Default")
      (node (ref "U3") (pin "44") (pinfunction "PA25_44") (pintype "bidirectional"))
    )
    (net (code "101") (name "unconnected-(U3-PA26-Pad45)") (class "Default")
      (node (ref "U3") (pin "45") (pinfunction "PA26_45") (pintype "bidirectional"))
    )
    (net (code "102") (name "unconnected-(U3-PA27-Pad46)") (class "Default")
      (node (ref "U3") (pin "46") (pinfunction "PA27_46") (pintype "bidirectional"))
    )
    (net (code "103") (name "unconnected-(U3-PB00-Pad140)") (class "Default")
      (node (ref "U3") (pin "140") (pinfunction "PB00_140") (pintype "bidirectional"))
    )
    (net (code "104") (name "unconnected-(U3-PB01-Pad141)") (class "Default")
      (node (ref "U3") (pin "141") (pinfunction "PB01_141") (pintype "bidirectional"))
    )
    (net (code "105") (name "unconnected-(U3-PB02-Pad143)") (class "Default")
      (node (ref "U3") (pin "143") (pinfunction "PB02_143") (pintype "bidirectional"))
    )
    (net (code "106") (name "unconnected-(U3-PB03-Pad144)") (class "Default")
      (node (ref "U3") (pin "144") (pinfunction "PB03_144") (pintype "bidirectional"))
    )
    (net (code "107") (name "unconnected-(U3-PB06-Pad9)") (class "Default")
      (node (ref "U3") (pin "9") (pinfunction "PB06_9") (pintype "bidirectional"))
    )
    (net (code "108") (name "unconnected-(U3-PB07-Pad10)") (class "Default")
      (node (ref "U3") (pin "10") (pinfunction "PB07_10") (pintype "bidirectional"))
    )
    (net (code "109") (name "unconnected-(U3-PB08-Pad11)") (class "Default")
      (node (ref "U3") (pin "11") (pinfunction "PB08_11") (pintype "bidirectional"))
    )
    (net (code "110") (name "unconnected-(U3-PB09-Pad12)") (class "Default")
      (node (ref "U3") (pin "12") (pinfunction "PB09_12") (pintype "bidirectional"))
    )
    (net (code "111") (name "unconnected-(U3-PB10-Pad13)") (class "Default")
      (node (ref "U3") (pin "13") (pinfunction "PB10_13") (pintype "bidirectional"))
    )
    (net (code "112") (name "unconnected-(U3-PB11-Pad14)") (class "Default")
      (node (ref "U3") (pin "14") (pinfunction "PB11_14") (pintype "bidirectional"))
    )
    (net (code "113") (name "unconnected-(U3-PB12-Pad15)") (class "Default")
      (node (ref "U3") (pin "15") (pinfunction "PB12_15") (pintype "bidirectional"))
    )
    (net (code "114") (name "unconnected-(U3-PB13-Pad16)") (class "Default")
      (node (ref "U3") (pin "16") (pinfunction "PB13_16") (pintype "bidirectional"))
    )
    (net (code "115") (name "unconnected-(U3-PB14-Pad17)") (class "Default")
      (node (ref "U3") (pin "17") (pinfunction "PB14_17") (pintype "bidirectional"))
    )
    (net (code "116") (name "unconnected-(U3-PB15-Pad18)") (class "Default")
      (node (ref "U3") (pin "18") (pinfunction "PB15_18") (pintype "bidirectional"))
    )
    (net (code "117") (name "unconnected-(U3-PB16-Pad19)") (class "Default")
      (node (ref "U3") (pin "19") (pinfunction "PB16_19") (pintype "bidirectional"))
    )
    (net (code "118") (name "unconnected-(U3-PB17-Pad20)") (class "Default")
      (node (ref "U3") (pin "20") (pinfunction "PB17_20") (pintype "bidirectional"))
    )
    (net (code "119") (name "unconnected-(U3-PB18-Pad57)") (class "Default")
      (node (ref "U3") (pin "57") (pinfunction "PB18_57") (pintype "bidirectional"))
    )
    (net (code "120") (name "unconnected-(U3-PB22-Pad61)") (class "Default")
      (node (ref "U3") (pin "61") (pinfunction "PB22_61") (pintype "bidirectional"))
    )
    (net (code "121") (name "unconnected-(U3-PB23-Pad62)") (class "Default")
      (node (ref "U3") (pin "62") (pinfunction "PB23_62") (pintype "bidirectional"))
    )
    (net (code "122") (name "unconnected-(U3-PB25-Pad64)") (class "Default")
      (node (ref "U3") (pin "64") (pinfunction "PB25_64") (pintype "bidirectional"))
    )
    (net (code "123") (name "unconnected-(U3-PB26-Pad65)") (class "Default")
      (node (ref "U3") (pin "65") (pinfunction "PB26_65") (pintype "bidirectional"))
    )
    (net (code "124") (name "unconnected-(U3-PB27-Pad66)") (class "Default")
      (node (ref "U3") (pin "66") (pinfunction "PB27_66") (pintype "bidirectional"))
    )
    (net (code "125") (name "unconnected-(U3-PB28-Pad67)") (class "Default")
      (node (ref "U3") (pin "67") (pinfunction "PB28_67") (pintype "bidirectional"))
    )
    (net (code "126") (name "unconnected-(U3-PB29-Pad68)") (class "Default")
      (node (ref "U3") (pin "68") (pinfunction "PB29_68") (pintype "bidirectional"))
    )
    (net (code "127") (name "unconnected-(U3-PC00-Pad71)") (class "Default")
      (node (ref "U3") (pin "71") (pinfunction "PC00_71") (pintype "bidirectional"))
    )
    (net (code "128") (name "unconnected-(U3-PC01-Pad72)") (class "Default")
      (node (ref "U3") (pin "72") (pinfunction "PC01_72") (pintype "bidirectional"))
    )
    (net (code "129") (name "unconnected-(U3-PC04-Pad77)") (class "Default")
      (node (ref "U3") (pin "77") (pinfunction "PC04_77") (pintype "bidirectional"))
    )
    (net (code "130") (name "unconnected-(U3-PC11-Pad84)") (class "Default")
      (node (ref "U3") (pin "84") (pinfunction "PC11_84") (pintype "bidirectional"))
    )
    (net (code "131") (name "unconnected-(U3-PC13-Pad86)") (class "Default")
      (node (ref "U3") (pin "86") (pinfunction "PC13_86") (pintype "bidirectional"))
    )
    (net (code "132") (name "unconnected-(U3-PC15-Pad88)") (class "Default")
      (node (ref "U3") (pin "88") (pinfunction "PC15_88") (pintype "bidirectional"))
    )
    (net (code "133") (name "unconnected-(U3-PD03-Pad110)") (class "Default")
      (node (ref "U3") (pin "110") (pinfunction "PD03_110") (pintype "bidirectional"))
    )
    (net (code "134") (name "unconnected-(U3-PD04-Pad111)") (class "Default")
      (node (ref "U3") (pin "111") (pinfunction "PD04_111") (pintype "bidirectional"))
    )
    (net (code "135") (name "unconnected-(U3-PD05-Pad112)") (class "Default")
      (node (ref "U3") (pin "112") (pinfunction "PD05_112") (pintype "bidirectional"))
    )
    (net (code "136") (name "unconnected-(U3-PD06-Pad113)") (class "Default")
      (node (ref "U3") (pin "113") (pinfunction "PD06_113") (pintype "bidirectional"))
    )
    (net (code "137") (name "unconnected-(U3-PD07-Pad114)") (class "Default")
      (node (ref "U3") (pin "114") (pinfunction "PD07_114") (pintype "bidirectional"))
    )
    (net (code "138") (name "unconnected-(U3-PD09-Pad116)") (class "Default")
      (node (ref "U3") (pin "116") (pinfunction "PD09_116") (pintype "bidirectional"))
    )
    (net (code "139") (name "unconnected-(U3-PD10-Pad117)") (class "Default")
      (node (ref "U3") (pin "117") (pinfunction "PD10_117") (pintype "bidirectional"))
    )
    (net (code "140") (name "unconnected-(U3-PD11-Pad120)") (class "Default")
      (node (ref "U3") (pin "120") (pinfunction "PD11_120") (pintype "bidirectional"))
    )
    (net (code "141") (name "unconnected-(U3-PD12-Pad121)") (class "Default")
      (node (ref "U3") (pin "121") (pinfunction "PD12_121") (pintype "bidirectional"))
    )
    (net (code "142") (name "unconnected-(U3-PD13-Pad122)") (class "Default")
      (node (ref "U3") (pin "122") (pinfunction "PD13_122") (pintype "bidirectional"))
    )
    (net (code "143") (name "unconnected-(U3-PD14-Pad123)") (class "Default")
      (node (ref "U3") (pin "123") (pinfunction "PD14_123") (pintype "bidirectional"))
    )
    (net (code "144") (name "unconnected-(U3-PD23-Pad132)") (class "Default")
      (node (ref "U3") (pin "132") (pinfunction "PD23_132") (pintype "bidirectional"))
    )
    (net (code "145") (name "unconnected-(U3-PD24-Pad133)") (class "Default")
      (node (ref "U3") (pin "133") (pinfunction "PD24_133") (pintype "bidirectional"))
    )
    (net (code "146") (name "unconnected-(U3-PD30-Pad139)") (class "Default")
      (node (ref "U3") (pin "139") (pinfunction "PD30_139") (pintype "bidirectional"))
    )
    (net (code "147") (name "unconnected-(U3-VBUS-Pad49)") (class "Default")
      (node (ref "U3") (pin "49") (pinfunction "VBUS_49") (pintype "bidirectional"))
    )
    (net (code "148") (name "unconnected-(U4-VREF-Pad5)") (class "Default")
      (node (ref "U4") (pin "5") (pinfunction "VREF_5") (pintype "bidirectional"))
    )
    (net (code "149") (name "~{TFT_CS}") (class "Default")
      (node (ref "J4") (pin "9") (pinfunction "9_9") (pintype "bidirectional"))
      (node (ref "U3") (pin "79") (pinfunction "PC06_79") (pintype "bidirectional"))
    )
    (net (code "150") (name "~{TFT_RD}") (class "Default")
      (node (ref "J4") (pin "12") (pinfunction "12_12") (pintype "bidirectional"))
      (node (ref "U3") (pin "83") (pinfunction "PC10_83") (pintype "bidirectional"))
    )
    (net (code "151") (name "~{TFT_RESET}") (class "Default")
      (node (ref "J4") (pin "8") (pinfunction "8_8") (pintype "bidirectional"))
      (node (ref "U3") (pin "115") (pinfunction "PD08_115") (pintype "bidirectional"))
      (node (ref "U3") (pin "81") (pinfunction "PC08_81") (pintype "bidirectional"))
    )
    (net (code "152") (name "~{TFT_WR}") (class "Default")
      (node (ref "J4") (pin "11") (pinfunction "11_11") (pintype "bidirectional"))
      (node (ref "U3") (pin "78") (pinfunction "PC05_78") (pintype "bidirectional"))
    )
  )
)
